# SnowFlake.net
KiCad netlist of a schematic drawn in EAGLE
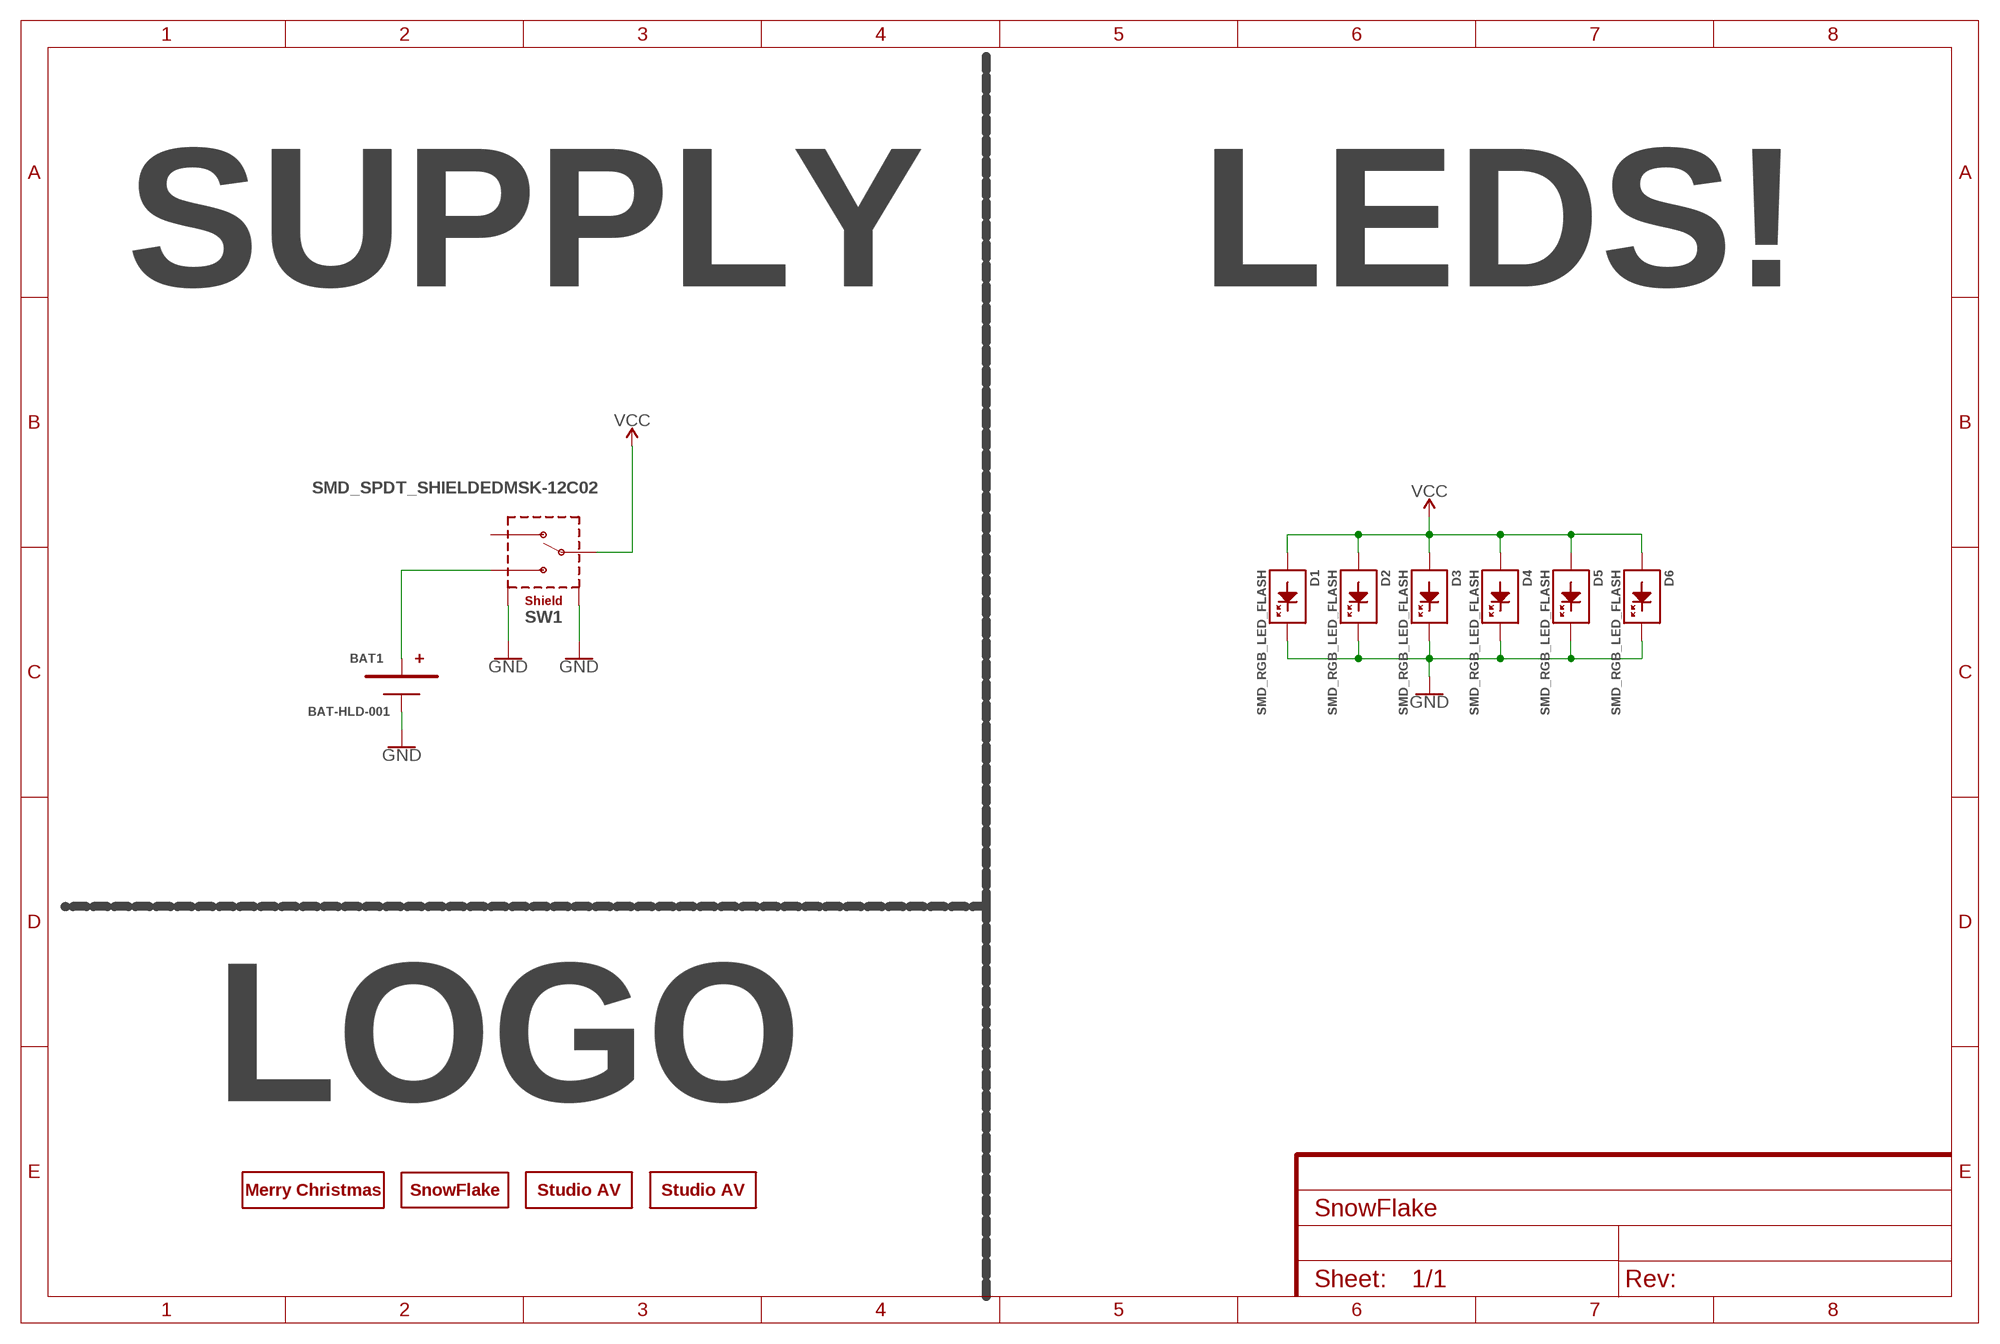
[diagram p0: schematic, sheet 1]

(export (version "E")
  (design (tool "Eeschema 10.0.6"))
  (components
    (comp (ref "BAT1")
      (value "BAT-HLD-001")
      (footprint "eagle-import:BATHLD001")
      (fields
        (field (name "MANUFACTURER#PART") "BAT-HLD-001-TR ")
        (field (name "MOUSER#PART") "712-BAT-HLD-001-TR ")
      )
      (libsource (lib "eagle-import") (part "BAT-HLD-001"))
    )
    (comp (ref "D1")
      (value "SMD_RGB_LED_FLASH")
      (footprint "eagle-import:SMD_RGB_LED_0807")
      (libsource (lib "eagle-import") (part "SMD_RGB_LED_FLASH"))
    )
    (comp (ref "D2")
      (value "SMD_RGB_LED_FLASH")
      (footprint "eagle-import:SMD_RGB_LED_0807")
      (libsource (lib "eagle-import") (part "SMD_RGB_LED_FLASH"))
    )
    (comp (ref "D3")
      (value "SMD_RGB_LED_FLASH")
      (footprint "eagle-import:SMD_RGB_LED_0807")
      (libsource (lib "eagle-import") (part "SMD_RGB_LED_FLASH"))
    )
    (comp (ref "D4")
      (value "SMD_RGB_LED_FLASH")
      (footprint "eagle-import:SMD_RGB_LED_0807")
      (libsource (lib "eagle-import") (part "SMD_RGB_LED_FLASH"))
    )
    (comp (ref "D5")
      (value "SMD_RGB_LED_FLASH")
      (footprint "eagle-import:SMD_RGB_LED_0807")
      (libsource (lib "eagle-import") (part "SMD_RGB_LED_FLASH"))
    )
    (comp (ref "D6")
      (value "SMD_RGB_LED_FLASH")
      (footprint "eagle-import:SMD_RGB_LED_0807")
      (libsource (lib "eagle-import") (part "SMD_RGB_LED_FLASH"))
    )
    (comp (ref "SW1")
      (value "SMD_SPDT_SHIELDEDMSK-12C02")
      (footprint "eagle-import:MSK-12C02")
      (libsource (lib "eagle-import") (part "SMD_SPDT_SHIELDEDMSK-12C02"))
    )
    (comp (ref "U$1")
      (value "MERRY_CHRISTMAS")
      (footprint "eagle-import:MERRY_CHRISTMAS")
      (libsource (lib "eagle-import") (part "MERRY_CHRISTMAS"))
    )
    (comp (ref "U$2")
      (value "STUDIO_AV-QR_CODE")
      (footprint "eagle-import:STUDIO_AV_QR")
      (libsource (lib "eagle-import") (part "STUDIO_AV-QR_CODE"))
    )
    (comp (ref "U$3")
      (value "STUDIO_AV-GENERAL")
      (footprint "eagle-import:STUDIO_AV")
      (libsource (lib "eagle-import") (part "STUDIO_AV-GENERAL"))
    )
    (comp (ref "U$4")
      (value "SNOWFLAKE")
      (footprint "eagle-import:SNOWFLAKE")
      (libsource (lib "eagle-import") (part "SNOWFLAKE"))
    )
  )
  (nets
    (net (code "1") (name "GND") (class "Default")
      (node (ref "BAT1") (pin "3") (pinfunction "N_3") (pintype "bidirectional"))
      (node (ref "D1") (pin "3") (pinfunction "K_3") (pintype "bidirectional"))
      (node (ref "D1") (pin "4") (pinfunction "K_4") (pintype "bidirectional"))
      (node (ref "D2") (pin "3") (pinfunction "K_3") (pintype "bidirectional"))
      (node (ref "D2") (pin "4") (pinfunction "K_4") (pintype "bidirectional"))
      (node (ref "D3") (pin "3") (pinfunction "K_3") (pintype "bidirectional"))
      (node (ref "D3") (pin "4") (pinfunction "K_4") (pintype "bidirectional"))
      (node (ref "D4") (pin "3") (pinfunction "K_3") (pintype "bidirectional"))
      (node (ref "D4") (pin "4") (pinfunction "K_4") (pintype "bidirectional"))
      (node (ref "D5") (pin "3") (pinfunction "K_3") (pintype "bidirectional"))
      (node (ref "D5") (pin "4") (pinfunction "K_4") (pintype "bidirectional"))
      (node (ref "D6") (pin "3") (pinfunction "K_3") (pintype "bidirectional"))
      (node (ref "D6") (pin "4") (pinfunction "K_4") (pintype "bidirectional"))
      (node (ref "SW1") (pin "GND@1") (pinfunction "S1_GND@1") (pintype "bidirectional"))
      (node (ref "SW1") (pin "GND@2") (pinfunction "S2_GND@2") (pintype "bidirectional"))
      (node (ref "SW1") (pin "GND@3") (pinfunction "S1_GND@3") (pintype "bidirectional"))
      (node (ref "SW1") (pin "GND@4") (pinfunction "S2_GND@4") (pintype "bidirectional"))
    )
    (net (code "2") (name "Net-(SW1-NO)") (class "Default")
      (node (ref "BAT1") (pin "1") (pinfunction "P_1") (pintype "bidirectional"))
      (node (ref "BAT1") (pin "2") (pinfunction "P_2") (pintype "bidirectional"))
      (node (ref "SW1") (pin "L2") (pinfunction "NO_L2") (pintype "passive"))
    )
    (net (code "3") (name "VCC") (class "Default")
      (node (ref "D1") (pin "1") (pinfunction "A_1") (pintype "bidirectional"))
      (node (ref "D1") (pin "2") (pinfunction "A_2") (pintype "bidirectional"))
      (node (ref "D2") (pin "1") (pinfunction "A_1") (pintype "bidirectional"))
      (node (ref "D2") (pin "2") (pinfunction "A_2") (pintype "bidirectional"))
      (node (ref "D3") (pin "1") (pinfunction "A_1") (pintype "bidirectional"))
      (node (ref "D3") (pin "2") (pinfunction "A_2") (pintype "bidirectional"))
      (node (ref "D4") (pin "1") (pinfunction "A_1") (pintype "bidirectional"))
      (node (ref "D4") (pin "2") (pinfunction "A_2") (pintype "bidirectional"))
      (node (ref "D5") (pin "1") (pinfunction "A_1") (pintype "bidirectional"))
      (node (ref "D5") (pin "2") (pinfunction "A_2") (pintype "bidirectional"))
      (node (ref "D6") (pin "1") (pinfunction "A_1") (pintype "bidirectional"))
      (node (ref "D6") (pin "2") (pinfunction "A_2") (pintype "bidirectional"))
      (node (ref "SW1") (pin "COM") (pinfunction "C_COM") (pintype "passive"))
    )
    (net (code "4") (name "unconnected-(SW1-NC-PadL1)") (class "Default")
      (node (ref "SW1") (pin "L1") (pinfunction "NC_L1") (pintype "passive"))
    )
  )
)
